# An_lisis_AC.net
KiCad netlist of a schematic drawn in Altium Designer
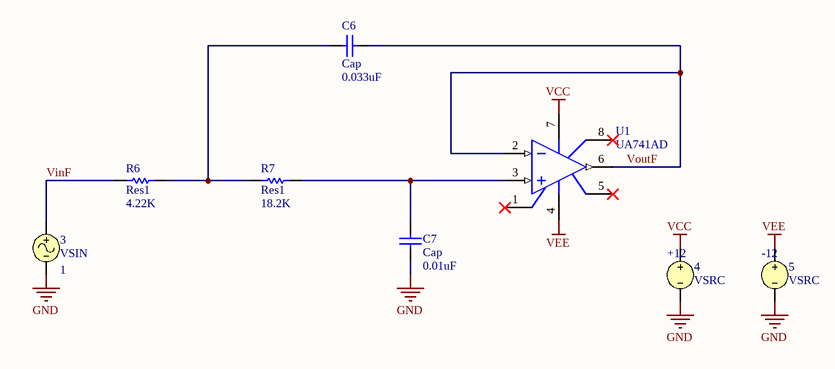
[diagram p0: Análisis_AC.SchDoc]

(export (version "E")
  (design (tool "Eeschema 10.0.6"))
  (components
    (comp (ref "3")
      (value "VSIN")
      (description "Sinusoidal Voltage Source")
      (fields (field (name "AMPLITUDE") "1") (field (name "PUBLISHER") "Altium Limited"))
      (libsource (lib "Simulation Sources") (part "VSIN"))
    )
    (comp (ref "4")
      (value "VSRC")
      (description "Voltage Source")
      (fields (field (name "ALTIUM_VALUE") "+12") (field (name "PUBLISHER") "Altium Limited"))
      (libsource (lib "Simulation Sources") (part "VSRC"))
    )
    (comp (ref "5")
      (value "VSRC")
      (description "Voltage Source")
      (fields (field (name "ALTIUM_VALUE") "-12") (field (name "PUBLISHER") "Altium Limited"))
      (libsource (lib "Simulation Sources") (part "VSRC"))
    )
    (comp (ref "C6")
      (value "Cap")
      (footprint "RAD-0.3")
      (description "Capacitor")
      (fields (field (name "ALTIUM_VALUE") "0.033uF") (field (name "PUBLISHER") "Altium Limited"))
      (libsource (lib "Miscellaneous Devices") (part "Cap"))
    )
    (comp (ref "C7")
      (value "Cap")
      (footprint "RAD-0.3")
      (description "Capacitor")
      (fields (field (name "ALTIUM_VALUE") "0.01uF") (field (name "PUBLISHER") "Altium Limited"))
      (libsource (lib "Miscellaneous Devices") (part "Cap"))
    )
    (comp (ref "R6")
      (value "Res1")
      (footprint "AXIAL-0.3")
      (description "Resistor")
      (fields (field (name "ALTIUM_VALUE") "4.22K") (field (name "PUBLISHER") "Altium Limited"))
      (libsource (lib "Miscellaneous Devices") (part "Res1"))
    )
    (comp (ref "R7")
      (value "Res1")
      (footprint "AXIAL-0.3")
      (description "Resistor")
      (fields (field (name "ALTIUM_VALUE") "18.2K") (field (name "PUBLISHER") "Altium Limited"))
      (libsource (lib "Miscellaneous Devices") (part "Res1"))
    )
    (comp (ref "U1")
      (value "UA741AD")
      (footprint "SO8_L")
      (description "General-Purpose Single Operational Amplifier")
      (fields (field (name "PUBLISHER") "Altium Limited"))
      (libsource (lib "altium-import") (part "root_0_UA741AD_"))
    )
  )
  (nets
    (net (code "1") (name "/VinF") (class "Default")
      (node (ref "3") (pin "1") (pinfunction "1_1") (pintype "passive"))
      (node (ref "R6") (pin "1") (pinfunction "1_1") (pintype "passive"))
    )
    (net (code "2") (name "/VoutF") (class "Default")
      (node (ref "C6") (pin "2") (pinfunction "2_2") (pintype "passive"))
      (node (ref "U1") (pin "2") (pinfunction "IN-_2") (pintype "input"))
      (node (ref "U1") (pin "6") (pinfunction "OUT_6") (pintype "output"))
    )
    (net (code "3") (name "GND") (class "Default")
      (node (ref "3") (pin "2") (pinfunction "2_2") (pintype "passive"))
      (node (ref "4") (pin "2") (pinfunction "2_2") (pintype "passive"))
      (node (ref "5") (pin "2") (pinfunction "2_2") (pintype "passive"))
      (node (ref "C7") (pin "2") (pinfunction "2_2") (pintype "passive"))
    )
    (net (code "4") (name "Net-(C6-Pad1)") (class "Default")
      (node (ref "C6") (pin "1") (pinfunction "1_1") (pintype "passive"))
      (node (ref "R6") (pin "2") (pinfunction "2_2") (pintype "passive"))
      (node (ref "R7") (pin "1") (pinfunction "1_1") (pintype "passive"))
    )
    (net (code "5") (name "Net-(U1-IN+)") (class "Default")
      (node (ref "C7") (pin "1") (pinfunction "1_1") (pintype "passive"))
      (node (ref "R7") (pin "2") (pinfunction "2_2") (pintype "passive"))
      (node (ref "U1") (pin "3") (pinfunction "IN+_3") (pintype "input"))
    )
    (net (code "6") (name "VCC") (class "Default")
      (node (ref "4") (pin "1") (pinfunction "1_1") (pintype "passive"))
      (node (ref "U1") (pin "7") (pinfunction "V+_7") (pintype "power_in"))
    )
    (net (code "7") (name "VEE") (class "Default")
      (node (ref "5") (pin "1") (pinfunction "1_1") (pintype "passive"))
      (node (ref "U1") (pin "4") (pinfunction "V-_4") (pintype "power_in"))
    )
    (net (code "8") (name "unconnected-(U1-NC-Pad8)") (class "Default")
      (node (ref "U1") (pin "8") (pinfunction "NC_8") (pintype "passive+no_connect"))
    )
    (net (code "9") (name "unconnected-(U1-OS_NULL-Pad1)") (class "Default")
      (node (ref "U1") (pin "1") (pinfunction "OS_NULL_1") (pintype "passive+no_connect"))
    )
    (net (code "10") (name "unconnected-(U1-OS_NULL-Pad5)") (class "Default")
      (node (ref "U1") (pin "5") (pinfunction "OS_NULL_5") (pintype "passive+no_connect"))
    )
  )
)
